# volcoder.net
KiCad netlist of a schematic drawn in EAGLE
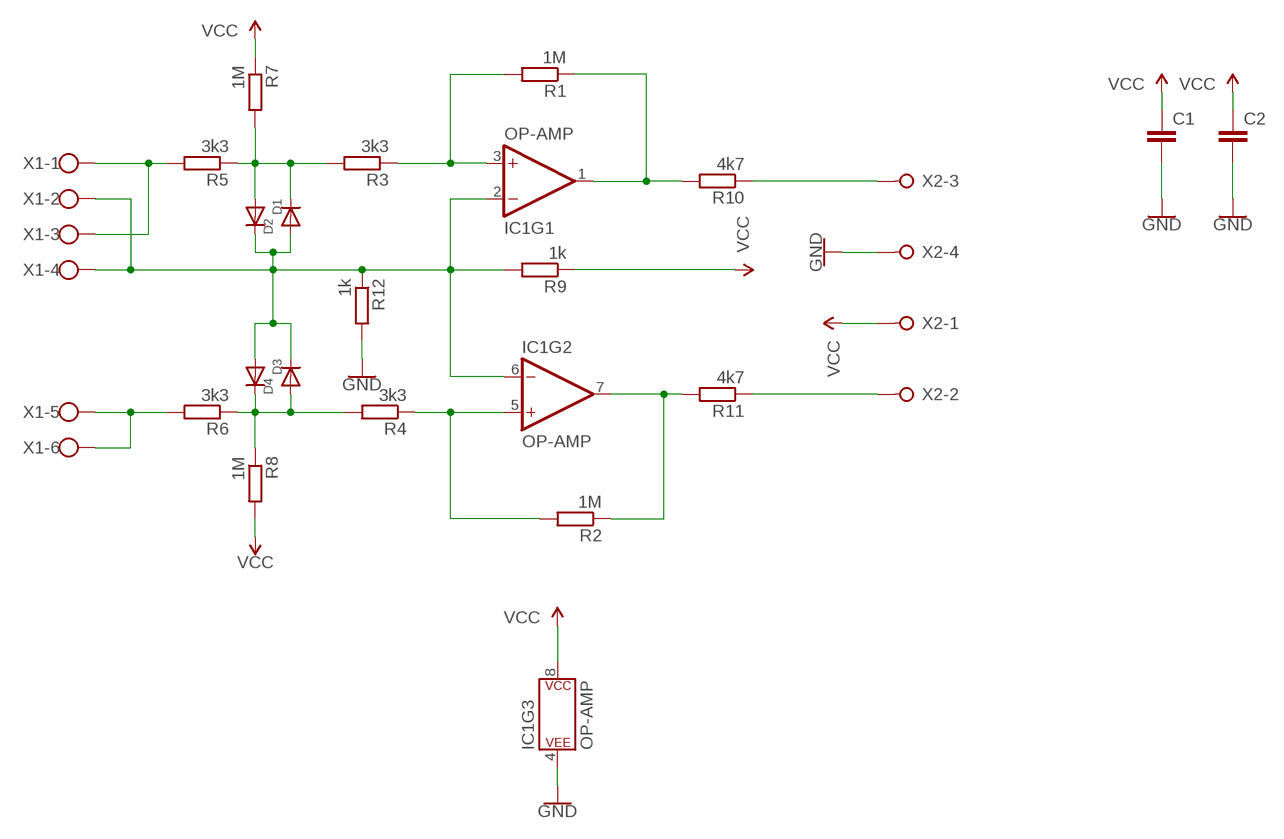
[diagram p0: schematic, sheet 1]

(export (version "E")
  (design (tool "Eeschema 10.0.6"))
  (components
    (comp (ref "C1")
      (value "C-EUC0805")
      (footprint "eagle-import:C0805")
      (libsource (lib "eagle-import") (part "C-EUC0805"))
    )
    (comp (ref "C2")
      (value "C-EUC0805")
      (footprint "eagle-import:C0805")
      (libsource (lib "eagle-import") (part "C-EUC0805"))
    )
    (comp (ref "D1")
      (value "DIODE_SOD-123FL")
      (footprint "eagle-import:SOD-123FL")
      (libsource (lib "eagle-import") (part "DIODE_SOD-123FL"))
    )
    (comp (ref "D2")
      (value "DIODE_SOD-123FL")
      (footprint "eagle-import:SOD-123FL")
      (libsource (lib "eagle-import") (part "DIODE_SOD-123FL"))
    )
    (comp (ref "D3")
      (value "DIODE_SOD-123FL")
      (footprint "eagle-import:SOD-123FL")
      (libsource (lib "eagle-import") (part "DIODE_SOD-123FL"))
    )
    (comp (ref "D4")
      (value "DIODE_SOD-123FL")
      (footprint "eagle-import:SOD-123FL")
      (libsource (lib "eagle-import") (part "DIODE_SOD-123FL"))
    )
    (comp (ref "IC1")
      (value "OP-AMP")
      (footprint "eagle-import:SO08")
      (libsource (lib "eagle-import") (part "OPAMP-DUALU"))
    )
    (comp (ref "R1")
      (value "1M")
      (footprint "eagle-import:R0805")
      (libsource (lib "eagle-import") (part "R-EU_R0805"))
    )
    (comp (ref "R2")
      (value "1M")
      (footprint "eagle-import:R0805")
      (libsource (lib "eagle-import") (part "R-EU_R0805"))
    )
    (comp (ref "R3")
      (value "3k3")
      (footprint "eagle-import:R0805")
      (libsource (lib "eagle-import") (part "R-EU_R0805"))
    )
    (comp (ref "R4")
      (value "3k3")
      (footprint "eagle-import:R0805")
      (libsource (lib "eagle-import") (part "R-EU_R0805"))
    )
    (comp (ref "R5")
      (value "3k3")
      (footprint "eagle-import:R0805")
      (libsource (lib "eagle-import") (part "R-EU_R0805"))
    )
    (comp (ref "R6")
      (value "3k3")
      (footprint "eagle-import:R0805")
      (libsource (lib "eagle-import") (part "R-EU_R0805"))
    )
    (comp (ref "R7")
      (value "1M")
      (footprint "eagle-import:R0805")
      (libsource (lib "eagle-import") (part "R-EU_R0805"))
    )
    (comp (ref "R8")
      (value "1M")
      (footprint "eagle-import:M0805")
      (libsource (lib "eagle-import") (part "R-EU_M0805"))
    )
    (comp (ref "R9")
      (value "1k")
      (footprint "eagle-import:R0805")
      (libsource (lib "eagle-import") (part "R-EU_R0805"))
    )
    (comp (ref "R10")
      (value "4k7")
      (footprint "eagle-import:R0805")
      (libsource (lib "eagle-import") (part "R-EU_R0805"))
    )
    (comp (ref "R11")
      (value "4k7")
      (footprint "eagle-import:R0805")
      (libsource (lib "eagle-import") (part "R-EU_R0805"))
    )
    (comp (ref "R12")
      (value "1k")
      (footprint "eagle-import:M0805")
      (libsource (lib "eagle-import") (part "R-EU_M0805"))
    )
    (comp (ref "X1")
      (value "W237-136")
      (footprint "eagle-import:W237-136")
      (fields (field (name "MPN") "237-136"))
      (libsource (lib "eagle-import") (part "W237-136"))
    )
    (comp (ref "X2")
      (value "W237-04P")
      (footprint "eagle-import:W237-4P")
      (libsource (lib "eagle-import") (part "W237-04P"))
    )
  )
  (nets
    (net (code "1") (name "GND") (class "Default")
      (node (ref "C1") (pin "2") (pinfunction "2_2") (pintype "passive"))
      (node (ref "C2") (pin "2") (pinfunction "2_2") (pintype "passive"))
      (node (ref "IC1") (pin "4") (pinfunction "P$V-_4") (pintype "bidirectional"))
      (node (ref "R12") (pin "2") (pinfunction "2_2") (pintype "passive"))
      (node (ref "X2") (pin "4") (pinfunction "KL_4") (pintype "passive"))
    )
    (net (code "2") (name "Net-(D1-PadA)") (class "Default")
      (node (ref "D1") (pin "A") (pinfunction "A_A") (pintype "passive"))
      (node (ref "D2") (pin "C") (pinfunction "C_C") (pintype "passive"))
      (node (ref "R3") (pin "2") (pinfunction "2_2") (pintype "passive"))
      (node (ref "R5") (pin "1") (pinfunction "1_1") (pintype "passive"))
      (node (ref "R7") (pin "2") (pinfunction "2_2") (pintype "passive"))
    )
    (net (code "3") (name "Net-(D3-PadC)") (class "Default")
      (node (ref "D3") (pin "C") (pinfunction "C_C") (pintype "passive"))
      (node (ref "D4") (pin "A") (pinfunction "A_A") (pintype "passive"))
      (node (ref "R4") (pin "2") (pinfunction "2_2") (pintype "passive"))
      (node (ref "R6") (pin "1") (pinfunction "1_1") (pintype "passive"))
      (node (ref "R8") (pin "1") (pinfunction "1_1") (pintype "passive"))
    )
    (net (code "4") (name "Net-(IC1A-+IN)") (class "Default")
      (node (ref "IC1") (pin "3") (pinfunction "+IN_3") (pintype "input"))
      (node (ref "R1") (pin "2") (pinfunction "2_2") (pintype "passive"))
      (node (ref "R3") (pin "1") (pinfunction "1_1") (pintype "passive"))
    )
    (net (code "5") (name "Net-(IC1A--IN)") (class "Default")
      (node (ref "D1") (pin "C") (pinfunction "C_C") (pintype "passive"))
      (node (ref "D2") (pin "A") (pinfunction "A_A") (pintype "passive"))
      (node (ref "D3") (pin "A") (pinfunction "A_A") (pintype "passive"))
      (node (ref "D4") (pin "C") (pinfunction "C_C") (pintype "passive"))
      (node (ref "IC1") (pin "2") (pinfunction "-IN_2") (pintype "input"))
      (node (ref "IC1") (pin "6") (pinfunction "-IN_6") (pintype "input"))
      (node (ref "R12") (pin "1") (pinfunction "1_1") (pintype "passive"))
      (node (ref "R9") (pin "2") (pinfunction "2_2") (pintype "passive"))
      (node (ref "X1") (pin "2") (pinfunction "KL_2") (pintype "passive"))
      (node (ref "X1") (pin "4") (pinfunction "KL_4") (pintype "passive"))
    )
    (net (code "6") (name "Net-(IC1A-OUT)") (class "Default")
      (node (ref "IC1") (pin "1") (pinfunction "OUT_1") (pintype "output"))
      (node (ref "R1") (pin "1") (pinfunction "1_1") (pintype "passive"))
      (node (ref "R10") (pin "2") (pinfunction "2_2") (pintype "passive"))
    )
    (net (code "7") (name "Net-(IC1B-+IN)") (class "Default")
      (node (ref "IC1") (pin "5") (pinfunction "+IN_5") (pintype "input"))
      (node (ref "R2") (pin "2") (pinfunction "2_2") (pintype "passive"))
      (node (ref "R4") (pin "1") (pinfunction "1_1") (pintype "passive"))
    )
    (net (code "8") (name "Net-(IC1B-OUT)") (class "Default")
      (node (ref "IC1") (pin "7") (pinfunction "OUT_7") (pintype "output"))
      (node (ref "R11") (pin "2") (pinfunction "2_2") (pintype "passive"))
      (node (ref "R2") (pin "1") (pinfunction "1_1") (pintype "passive"))
    )
    (net (code "9") (name "Net-(X1A-KL)") (class "Default")
      (node (ref "R5") (pin "2") (pinfunction "2_2") (pintype "passive"))
      (node (ref "X1") (pin "1") (pinfunction "KL_1") (pintype "passive"))
      (node (ref "X1") (pin "3") (pinfunction "KL_3") (pintype "passive"))
    )
    (net (code "10") (name "Net-(X1E-KL)") (class "Default")
      (node (ref "R6") (pin "2") (pinfunction "2_2") (pintype "passive"))
      (node (ref "X1") (pin "5") (pinfunction "KL_5") (pintype "passive"))
      (node (ref "X1") (pin "6") (pinfunction "KL_6") (pintype "passive"))
    )
    (net (code "11") (name "Net-(X2B-KL)") (class "Default")
      (node (ref "R11") (pin "1") (pinfunction "1_1") (pintype "passive"))
      (node (ref "X2") (pin "2") (pinfunction "KL_2") (pintype "passive"))
    )
    (net (code "12") (name "Net-(X2C-KL)") (class "Default")
      (node (ref "R10") (pin "1") (pinfunction "1_1") (pintype "passive"))
      (node (ref "X2") (pin "3") (pinfunction "KL_3") (pintype "passive"))
    )
    (net (code "13") (name "VCC") (class "Default")
      (node (ref "C1") (pin "1") (pinfunction "1_1") (pintype "passive"))
      (node (ref "C2") (pin "1") (pinfunction "1_1") (pintype "passive"))
      (node (ref "IC1") (pin "8") (pinfunction "P$V+_8") (pintype "bidirectional"))
      (node (ref "R7") (pin "1") (pinfunction "1_1") (pintype "passive"))
      (node (ref "R8") (pin "2") (pinfunction "2_2") (pintype "passive"))
      (node (ref "R9") (pin "1") (pinfunction "1_1") (pintype "passive"))
      (node (ref "X2") (pin "1") (pinfunction "KL_1") (pintype "passive"))
    )
  )
)
